# Schematic2_new.net
KiCad netlist of a schematic drawn in Altium Designer
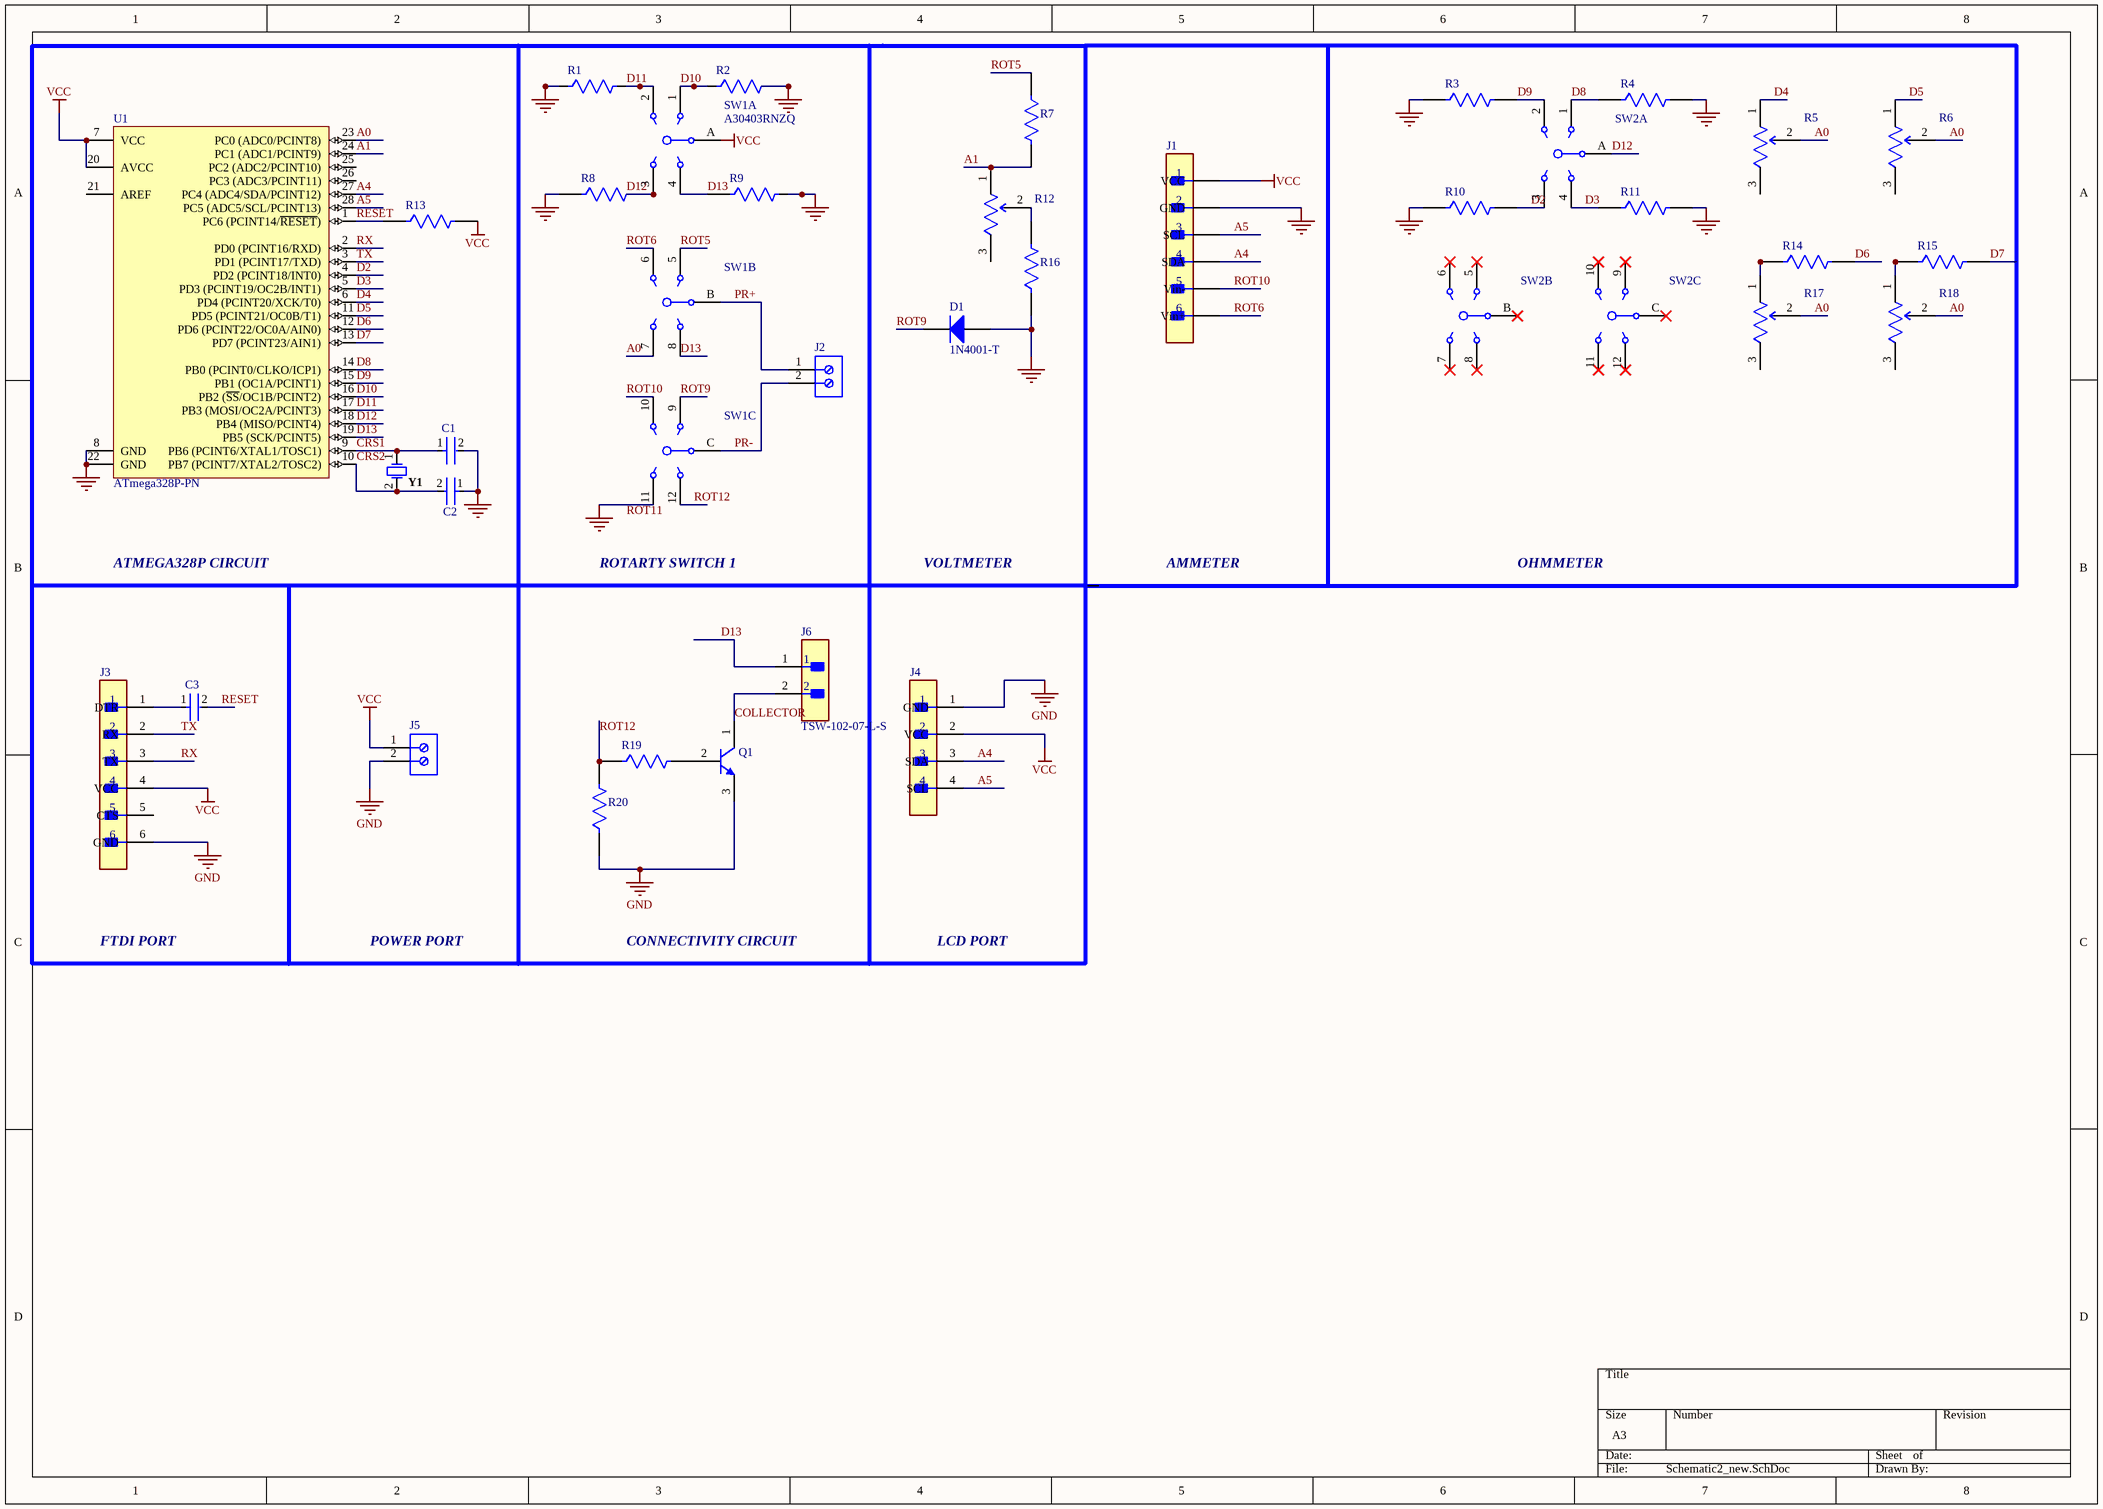
[diagram p0: Schematic2_new.SchDoc]

(export (version "E")
  (design (tool "Eeschema 10.0.6"))
  (components
    (comp (ref "C1")
      (value "RDE5C1H220J0K1H03B")
      (footprint "FP-RDE0M1-MFG")
      (description "Ceramic Capacitor 22pF ±5% 50V C0G Radial")
      (fields (field (name "TOLERANCE") "5%"))
      (libsource (lib "Altium Content Vault") (part "b4654b650e69147ec39a6b967a45e02"))
    )
    (comp (ref "C2")
      (value "RDE5C1H220J0K1H03B")
      (footprint "FP-RDE0M1-MFG")
      (description "Ceramic Capacitor 22pF ±5% 50V C0G Radial")
      (fields (field (name "TOLERANCE") "5%"))
      (libsource (lib "Altium Content Vault") (part "b4654b650e69147ec39a6b967a45e02"))
    )
    (comp (ref "C3")
      (value "RDE5C1H220J0K1H03B")
      (footprint "FP-RDE0M1-MFG")
      (description "Ceramic Capacitor 22pF ±5% 50V C0G Radial")
      (fields (field (name "TOLERANCE") "5%"))
      (libsource (lib "Altium Content Vault") (part "b4654b650e69147ec39a6b967a45e02"))
    )
    (comp (ref "D1")
      (value "1N4001-T")
      (footprint "DIOD-DO-41-P-2_V")
      (description "1.0 A Rectifier, 15 pF, 50 V, -65 to 150 degC, 2-Pin DO-41 Plastic, RoHS, Tape and Reel")
      (fields (field (name "MANUFACTURER") "Diodes Inc"))
      (libsource (lib "Altium Content Vault") (part "DIOD-D-A1K2-2"))
    )
    (comp (ref "J1")
      (value "PEC06SBBN")
      (footprint "FP-PEC06SBBN-MFG")
      (description "CONN HEADER R/A 6POS 2.54MM")
      (libsource (lib "") (part "f2cb566baf1c37ab5a3b8e90bbeafd6_1"))
    )
    (comp (ref "J2")
      (value "691214110002")
      (footprint "691214110002")
      (description "Serie 2141 - 3.50 mm Horizontal Entry Modular with Rising Cage Clamp WR-TBL, 2 pin")
      (fields (field (name "MANUFACTURER") "Wurth Elektronik") (field (name "PUBLISHER") "WurthElektronik"))
      (libsource (lib "Altium Content Vault") (part "WE-CN-1P-F-TB2"))
    )
    (comp (ref "J3")
      (value "PEC06SBBN")
      (footprint "FP-PEC06SBBN-MFG")
      (description "CONN HEADER R/A 6POS 2.54MM")
      (libsource (lib "Altium Content Vault") (part "f2cb566baf1c37ab5a3b8e90bbeafd6"))
    )
    (comp (ref "J4")
      (value "MTLW-104-05-G-S-185")
      (footprint "FP-MTLW-104-05-G-S-185-MFG")
      (description "CONN HEADER VERT 4POS 2.54MM")
      (libsource (lib "Altium Content Vault") (part "299a8cea1bdcbc3624fe62c390fa72c"))
    )
    (comp (ref "J5")
      (value "691214110002")
      (footprint "691214110002")
      (description "Serie 2141 - 3.50 mm Horizontal Entry Modular with Rising Cage Clamp WR-TBL, 2 pin")
      (fields (field (name "MANUFACTURER") "Wurth Elektronik") (field (name "PUBLISHER") "WurthElektronik"))
      (libsource (lib "Altium Content Vault") (part "WE-CN-1P-F-TB2"))
    )
    (comp (ref "J6")
      (value "TSW-102-07-L-S")
      (footprint "FP-TSW-102-07-L-S-MFG")
      (description "CONN HEADER VERT 2POS 2.54MM")
      (libsource (lib "Altium Content Vault") (part "3bc925449376181038e59eaffc5286c"))
    )
    (comp (ref "Q1")
      (value "BC547BRL1G")
      (footprint "ONSC-TO-92-3-29-11_AM_BL")
      (description "Amplifier Transistor, NPN Silicon, 3-Pin TO-92, Pb-Free, Tape and Reel")
      (fields (field (name "MANUFACTURER") "On Semiconductor"))
      (libsource (lib "Altium Content Vault") (part "ONSC-NPN-C1B2E3-3"))
    )
    (comp (ref "R1")
      (value "G001R1000FE1280")
      (footprint "FP-G001R1000FE1280-MFG")
      (description "Res Wirewound 0.1 Ohm 1% 1W ±90ppm/°C Ceramic Hi Temp Sil AXL Thru-Hole Bulk")
      (fields (field (name "TOLERANCE") "1%"))
      (libsource (lib "Altium Content Vault") (part "1029c3af85768c4190bb7ad29bc67b5"))
    )
    (comp (ref "R2")
      (value "G001R1000FE1280")
      (footprint "FP-G001R1000FE1280-MFG")
      (description "Res Wirewound 0.1 Ohm 1% 1W ±90ppm/°C Ceramic Hi Temp Sil AXL Thru-Hole Bulk")
      (fields (field (name "TOLERANCE") "1%"))
      (libsource (lib "Altium Content Vault") (part "1029c3af85768c4190bb7ad29bc67b5"))
    )
    (comp (ref "R3")
      (value "G001R1000FE1280")
      (footprint "FP-G001R1000FE1280-MFG")
      (description "Res Wirewound 0.1 Ohm 1% 1W ±90ppm/°C Ceramic Hi Temp Sil AXL Thru-Hole Bulk")
      (fields (field (name "TOLERANCE") "1%"))
      (libsource (lib "Altium Content Vault") (part "1029c3af85768c4190bb7ad29bc67b5"))
    )
    (comp (ref "R4")
      (value "G001R1000FE1280")
      (footprint "FP-G001R1000FE1280-MFG")
      (description "Res Wirewound 0.1 Ohm 1% 1W ±90ppm/°C Ceramic Hi Temp Sil AXL Thru-Hole Bulk")
      (fields (field (name "TOLERANCE") "1%"))
      (libsource (lib "Altium Content Vault") (part "1029c3af85768c4190bb7ad29bc67b5"))
    )
    (comp (ref "R5")
      (value "3296W-1-103RLF")
      (footprint "FP-3296W-MFG")
      (description "TRIMMER 10K OHM 0.5W PC PIN TOP")
      (fields (field (name "TOLERANCE") "10%"))
      (libsource (lib "Altium Content Vault") (part "194907ebf2981c0cdd5d9631a0af656"))
    )
    (comp (ref "R6")
      (value "3296W-1-103RLF")
      (footprint "FP-3296W-MFG")
      (description "TRIMMER 10K OHM 0.5W PC PIN TOP")
      (fields (field (name "TOLERANCE") "10%"))
      (libsource (lib "Altium Content Vault") (part "194907ebf2981c0cdd5d9631a0af656"))
    )
    (comp (ref "R7")
      (value "G001R1000FE1280")
      (footprint "FP-G001R1000FE1280-MFG")
      (description "Res Wirewound 0.1 Ohm 1% 1W ±90ppm/°C Ceramic Hi Temp Sil AXL Thru-Hole Bulk")
      (fields (field (name "TOLERANCE") "1%"))
      (libsource (lib "Altium Content Vault") (part "1029c3af85768c4190bb7ad29bc67b5"))
    )
    (comp (ref "R8")
      (value "G001R1000FE1280")
      (footprint "FP-G001R1000FE1280-MFG")
      (description "Res Wirewound 0.1 Ohm 1% 1W ±90ppm/°C Ceramic Hi Temp Sil AXL Thru-Hole Bulk")
      (fields (field (name "TOLERANCE") "1%"))
      (libsource (lib "Altium Content Vault") (part "1029c3af85768c4190bb7ad29bc67b5"))
    )
    (comp (ref "R9")
      (value "G001R1000FE1280")
      (footprint "FP-G001R1000FE1280-MFG")
      (description "Res Wirewound 0.1 Ohm 1% 1W ±90ppm/°C Ceramic Hi Temp Sil AXL Thru-Hole Bulk")
      (fields (field (name "TOLERANCE") "1%"))
      (libsource (lib "Altium Content Vault") (part "1029c3af85768c4190bb7ad29bc67b5"))
    )
    (comp (ref "R10")
      (value "G001R1000FE1280")
      (footprint "FP-G001R1000FE1280-MFG")
      (description "Res Wirewound 0.1 Ohm 1% 1W ±90ppm/°C Ceramic Hi Temp Sil AXL Thru-Hole Bulk")
      (fields (field (name "TOLERANCE") "1%"))
      (libsource (lib "Altium Content Vault") (part "1029c3af85768c4190bb7ad29bc67b5"))
    )
    (comp (ref "R11")
      (value "G001R1000FE1280")
      (footprint "FP-G001R1000FE1280-MFG")
      (description "Res Wirewound 0.1 Ohm 1% 1W ±90ppm/°C Ceramic Hi Temp Sil AXL Thru-Hole Bulk")
      (fields (field (name "TOLERANCE") "1%"))
      (libsource (lib "Altium Content Vault") (part "1029c3af85768c4190bb7ad29bc67b5"))
    )
    (comp (ref "R12")
      (value "3296W-1-103RLF")
      (footprint "FP-3296W-MFG")
      (description "TRIMMER 10K OHM 0.5W PC PIN TOP")
      (fields (field (name "TOLERANCE") "10%"))
      (libsource (lib "Altium Content Vault") (part "194907ebf2981c0cdd5d9631a0af656"))
    )
    (comp (ref "R13")
      (value "G001R1000FE1280")
      (footprint "FP-G001R1000FE1280-MFG")
      (description "Res Wirewound 0.1 Ohm 1% 1W ±90ppm/°C Ceramic Hi Temp Sil AXL Thru-Hole Bulk")
      (fields (field (name "TOLERANCE") "1%"))
      (libsource (lib "Altium Content Vault") (part "1029c3af85768c4190bb7ad29bc67b5"))
    )
    (comp (ref "R14")
      (value "G001R1000FE1280")
      (footprint "FP-G001R1000FE1280-MFG")
      (description "Res Wirewound 0.1 Ohm 1% 1W ±90ppm/°C Ceramic Hi Temp Sil AXL Thru-Hole Bulk")
      (fields (field (name "TOLERANCE") "1%"))
      (libsource (lib "Altium Content Vault") (part "1029c3af85768c4190bb7ad29bc67b5"))
    )
    (comp (ref "R15")
      (value "G001R1000FE1280")
      (footprint "FP-G001R1000FE1280-MFG")
      (description "Res Wirewound 0.1 Ohm 1% 1W ±90ppm/°C Ceramic Hi Temp Sil AXL Thru-Hole Bulk")
      (fields (field (name "TOLERANCE") "1%"))
      (libsource (lib "Altium Content Vault") (part "1029c3af85768c4190bb7ad29bc67b5"))
    )
    (comp (ref "R16")
      (value "G001R1000FE1280")
      (footprint "FP-G001R1000FE1280-MFG")
      (description "Res Wirewound 0.1 Ohm 1% 1W ±90ppm/°C Ceramic Hi Temp Sil AXL Thru-Hole Bulk")
      (fields (field (name "TOLERANCE") "1%"))
      (libsource (lib "Altium Content Vault") (part "1029c3af85768c4190bb7ad29bc67b5"))
    )
    (comp (ref "R17")
      (value "3296W-1-103RLF")
      (footprint "FP-3296W-MFG")
      (description "TRIMMER 10K OHM 0.5W PC PIN TOP")
      (fields (field (name "TOLERANCE") "10%"))
      (libsource (lib "Altium Content Vault") (part "194907ebf2981c0cdd5d9631a0af656"))
    )
    (comp (ref "R18")
      (value "3296W-1-103RLF")
      (footprint "FP-3296W-MFG")
      (description "TRIMMER 10K OHM 0.5W PC PIN TOP")
      (fields (field (name "TOLERANCE") "10%"))
      (libsource (lib "Altium Content Vault") (part "194907ebf2981c0cdd5d9631a0af656"))
    )
    (comp (ref "R19")
      (value "G001R1000FE1280")
      (footprint "FP-G001R1000FE1280-MFG")
      (description "Res Wirewound 0.1 Ohm 1% 1W ±90ppm/°C Ceramic Hi Temp Sil AXL Thru-Hole Bulk")
      (fields (field (name "TOLERANCE") "1%"))
      (libsource (lib "Altium Content Vault") (part "1029c3af85768c4190bb7ad29bc67b5"))
    )
    (comp (ref "R20")
      (value "G001R1000FE1280")
      (footprint "FP-G001R1000FE1280-MFG")
      (description "Res Wirewound 0.1 Ohm 1% 1W ±90ppm/°C Ceramic Hi Temp Sil AXL Thru-Hole Bulk")
      (fields (field (name "TOLERANCE") "1%"))
      (libsource (lib "Altium Content Vault") (part "1029c3af85768c4190bb7ad29bc67b5"))
    )
    (comp (ref "SW1")
      (value "A30403RNZQ")
      (footprint "CKCP-A30403RNZQ-15_V")
      (description "A Series Rotary Switch, 3 Poles, 4 Positions, 30 deg Angle of Throw, -30 to 85 degC, RoHS")
      (fields (field (name "MANUFACTURER") "C&K Components"))
      (libsource (lib "") (part "CKCP-SW_3P4T-15_2"))
    )
    (comp (ref "SW2")
      (value "A30403RNZQ")
      (footprint "CKCP-A30403RNZQ-15_V")
      (description "A Series Rotary Switch, 3 Poles, 4 Positions, 30 deg Angle of Throw, -30 to 85 degC, RoHS")
      (fields (field (name "MANUFACTURER") "C&K Components"))
      (libsource (lib "") (part "CKCP-SW_3P4T-15_1"))
    )
    (comp (ref "U1")
      (value "ATmega328P-PN")
      (footprint "28P3")
      (libsource (lib "Altium Content Vault") (part "MC-8B-ATM48-IL28"))
    )
    (comp (ref "Y1")
      (value "FOXSLF/160-20")
      (footprint "FOX-FOXSLF160-20")
      (description "Resistance Weld Thru-Hole Crystal, 16 MHz, -20 to 70 degC, 2-Pin THD, RoHS, Bulk")
      (fields (field (name "TOLERANCE") "1%"))
      (libsource (lib "Altium Content Vault") (part "XTAL-1-2-2"))
    )
  )
  (nets
    (net (code "1") (name "/A0") (class "Default")
      (node (ref "R17") (pin "2") (pinfunction "WIPER_2") (pintype "passive"))
      (node (ref "R18") (pin "2") (pinfunction "WIPER_2") (pintype "passive"))
      (node (ref "R5") (pin "2") (pinfunction "WIPER_2") (pintype "passive"))
      (node (ref "R6") (pin "2") (pinfunction "WIPER_2") (pintype "passive"))
      (node (ref "SW1") (pin "7") (pinfunction "7_7") (pintype "passive"))
      (node (ref "U1") (pin "23") (pinfunction "PC0_(ADC0/PCINT8)_23") (pintype "bidirectional"))
    )
    (net (code "2") (name "/A1") (class "Default")
      (node (ref "R12") (pin "1") (pinfunction "CCW_1") (pintype "passive"))
      (node (ref "R7") (pin "2") (pinfunction "2_2") (pintype "passive"))
      (node (ref "U1") (pin "24") (pinfunction "PC1_(ADC1/PCINT9)_24") (pintype "bidirectional"))
    )
    (net (code "3") (name "/A4") (class "Default")
      (node (ref "J1") (pin "4") (pinfunction "SDA_4") (pintype "passive"))
      (node (ref "J4") (pin "3") (pinfunction "SDA_3") (pintype "passive"))
      (node (ref "U1") (pin "27") (pinfunction "PC4_(ADC4/SDA/PCINT12)_27") (pintype "bidirectional"))
    )
    (net (code "4") (name "/A5") (class "Default")
      (node (ref "J1") (pin "3") (pinfunction "SCL_3") (pintype "passive"))
      (node (ref "J4") (pin "4") (pinfunction "SCL_4") (pintype "passive"))
      (node (ref "U1") (pin "28") (pinfunction "PC5_(ADC5/SCL/PCINT13)_28") (pintype "bidirectional"))
    )
    (net (code "5") (name "/COLLECTOR") (class "Default")
      (node (ref "J6") (pin "2") (pinfunction "2_2") (pintype "passive"))
      (node (ref "Q1") (pin "1") (pinfunction "C_1") (pintype "passive"))
    )
    (net (code "6") (name "/CRS1") (class "Default")
      (node (ref "C1") (pin "1") (pinfunction "1_1") (pintype "passive"))
      (node (ref "U1") (pin "9") (pinfunction "PB6_(PCINT6/XTAL1/TOSC1)_9") (pintype "bidirectional"))
      (node (ref "Y1") (pin "1") (pinfunction "1_1") (pintype "passive"))
    )
    (net (code "7") (name "/CRS2") (class "Default")
      (node (ref "C2") (pin "2") (pinfunction "2_2") (pintype "passive"))
      (node (ref "U1") (pin "10") (pinfunction "PB7_(PCINT7/XTAL2/TOSC2)_10") (pintype "bidirectional"))
      (node (ref "Y1") (pin "2") (pinfunction "2_2") (pintype "passive"))
    )
    (net (code "8") (name "/D2") (class "Default")
      (node (ref "R10") (pin "2") (pinfunction "2_2") (pintype "passive"))
      (node (ref "SW2") (pin "3") (pinfunction "3_3") (pintype "passive"))
      (node (ref "U1") (pin "4") (pinfunction "PD2_(PCINT18/INT0)_4") (pintype "bidirectional"))
    )
    (net (code "9") (name "/D3") (class "Default")
      (node (ref "R11") (pin "1") (pinfunction "1_1") (pintype "passive"))
      (node (ref "SW2") (pin "4") (pinfunction "4_4") (pintype "passive"))
      (node (ref "U1") (pin "5") (pinfunction "PD3_(PCINT19/OC2B/INT1)_5") (pintype "bidirectional"))
    )
    (net (code "10") (name "/D4") (class "Default")
      (node (ref "R5") (pin "1") (pinfunction "CCW_1") (pintype "passive"))
      (node (ref "U1") (pin "6") (pinfunction "PD4_(PCINT20/XCK/T0)_6") (pintype "bidirectional"))
    )
    (net (code "11") (name "/D5") (class "Default")
      (node (ref "R6") (pin "1") (pinfunction "CCW_1") (pintype "passive"))
      (node (ref "U1") (pin "11") (pinfunction "PD5_(PCINT21/OC0B/T1)_11") (pintype "bidirectional"))
    )
    (net (code "12") (name "/D6") (class "Default")
      (node (ref "R14") (pin "2") (pinfunction "2_2") (pintype "passive"))
      (node (ref "U1") (pin "12") (pinfunction "PD6_(PCINT22/OC0A/AIN0)_12") (pintype "bidirectional"))
    )
    (net (code "13") (name "/D7") (class "Default")
      (node (ref "R15") (pin "2") (pinfunction "2_2") (pintype "passive"))
      (node (ref "U1") (pin "13") (pinfunction "PD7_(PCINT23/AIN1)_13") (pintype "bidirectional"))
    )
    (net (code "14") (name "/D8") (class "Default")
      (node (ref "R4") (pin "1") (pinfunction "1_1") (pintype "passive"))
      (node (ref "SW2") (pin "1") (pinfunction "1_1") (pintype "passive"))
      (node (ref "U1") (pin "14") (pinfunction "PB0_(PCINT0/CLKO/ICP1)_14") (pintype "bidirectional"))
    )
    (net (code "15") (name "/D9") (class "Default")
      (node (ref "R3") (pin "2") (pinfunction "2_2") (pintype "passive"))
      (node (ref "SW2") (pin "2") (pinfunction "2_2") (pintype "passive"))
      (node (ref "U1") (pin "15") (pinfunction "PB1_(OC1A/PCINT1)_15") (pintype "bidirectional"))
    )
    (net (code "16") (name "/D10") (class "Default")
      (node (ref "R2") (pin "1") (pinfunction "1_1") (pintype "passive"))
      (node (ref "SW1") (pin "1") (pinfunction "1_1") (pintype "passive"))
      (node (ref "U1") (pin "16") (pinfunction "PB2_(~{SS}/OC1B/PCINT2)_16") (pintype "bidirectional"))
    )
    (net (code "17") (name "/D11") (class "Default")
      (node (ref "R1") (pin "2") (pinfunction "2_2") (pintype "passive"))
      (node (ref "SW1") (pin "2") (pinfunction "2_2") (pintype "passive"))
      (node (ref "U1") (pin "17") (pinfunction "PB3_(MOSI/OC2A/PCINT3)_17") (pintype "bidirectional"))
    )
    (net (code "18") (name "/D12") (class "Default")
      (node (ref "R8") (pin "2") (pinfunction "2_2") (pintype "passive"))
      (node (ref "SW1") (pin "3") (pinfunction "3_3") (pintype "passive"))
      (node (ref "SW2") (pin "A") (pinfunction "A_A") (pintype "passive"))
      (node (ref "U1") (pin "18") (pinfunction "PB4_(MISO/PCINT4)_18") (pintype "bidirectional"))
    )
    (net (code "19") (name "/D13") (class "Default")
      (node (ref "J6") (pin "1") (pinfunction "1_1") (pintype "passive"))
      (node (ref "R9") (pin "1") (pinfunction "1_1") (pintype "passive"))
      (node (ref "SW1") (pin "4") (pinfunction "4_4") (pintype "passive"))
      (node (ref "SW1") (pin "8") (pinfunction "8_8") (pintype "passive"))
      (node (ref "U1") (pin "19") (pinfunction "PB5_(SCK/PCINT5)_19") (pintype "bidirectional"))
    )
    (net (code "20") (name "/PR+") (class "Default")
      (node (ref "J2") (pin "1") (pinfunction "1_1") (pintype "passive"))
      (node (ref "SW1") (pin "B") (pinfunction "B_B") (pintype "passive"))
    )
    (net (code "21") (name "/PR-") (class "Default")
      (node (ref "J2") (pin "2") (pinfunction "2_2") (pintype "passive"))
      (node (ref "SW1") (pin "C") (pinfunction "C_C") (pintype "passive"))
    )
    (net (code "22") (name "/RESET") (class "Default")
      (node (ref "C3") (pin "2") (pinfunction "2_2") (pintype "passive"))
      (node (ref "R13") (pin "1") (pinfunction "1_1") (pintype "passive"))
      (node (ref "U1") (pin "1") (pinfunction "PC6_(PCINT14/~{RESET})_1") (pintype "bidirectional"))
    )
    (net (code "23") (name "/ROT5") (class "Default")
      (node (ref "R7") (pin "1") (pinfunction "1_1") (pintype "passive"))
      (node (ref "SW1") (pin "5") (pinfunction "5_5") (pintype "passive"))
    )
    (net (code "24") (name "/ROT6") (class "Default")
      (node (ref "J1") (pin "6") (pinfunction "Vin+_6") (pintype "passive"))
      (node (ref "SW1") (pin "6") (pinfunction "6_6") (pintype "passive"))
    )
    (net (code "25") (name "/ROT9") (class "Default")
      (node (ref "D1") (pin "2") (pinfunction "K_2") (pintype "passive"))
      (node (ref "SW1") (pin "9") (pinfunction "9_9") (pintype "passive"))
    )
    (net (code "26") (name "/ROT10") (class "Default")
      (node (ref "J1") (pin "5") (pinfunction "Vin-_5") (pintype "passive"))
      (node (ref "SW1") (pin "10") (pinfunction "10_10") (pintype "passive"))
    )
    (net (code "28") (name "/ROT12") (class "Default")
      (node (ref "R19") (pin "1") (pinfunction "1_1") (pintype "passive"))
      (node (ref "R20") (pin "2") (pinfunction "2_2") (pintype "passive"))
      (node (ref "SW1") (pin "12") (pinfunction "12_12") (pintype "passive"))
    )
    (net (code "29") (name "/RX") (class "Default")
      (node (ref "J3") (pin "3") (pinfunction "TX_3") (pintype "passive"))
      (node (ref "U1") (pin "2") (pinfunction "PD0_(PCINT16/RXD)_2") (pintype "bidirectional"))
    )
    (net (code "30") (name "/TX") (class "Default")
      (node (ref "J3") (pin "2") (pinfunction "RX_2") (pintype "passive"))
      (node (ref "U1") (pin "3") (pinfunction "PD1_(PCINT17/TXD)_3") (pintype "bidirectional"))
    )
    (net (code "31") (name "GND") (class "Default")
      (node (ref "C1") (pin "2") (pinfunction "2_2") (pintype "passive"))
      (node (ref "C2") (pin "1") (pinfunction "1_1") (pintype "passive"))
      (node (ref "D1") (pin "1") (pinfunction "A_1") (pintype "passive"))
      (node (ref "J1") (pin "2") (pinfunction "GND_2") (pintype "passive"))
      (node (ref "J3") (pin "6") (pinfunction "GND_6") (pintype "passive"))
      (node (ref "J4") (pin "1") (pinfunction "GND_1") (pintype "passive"))
      (node (ref "J5") (pin "2") (pinfunction "2_2") (pintype "passive"))
      (node (ref "Q1") (pin "3") (pinfunction "E_3") (pintype "passive"))
      (node (ref "R1") (pin "1") (pinfunction "1_1") (pintype "passive"))
      (node (ref "R10") (pin "1") (pinfunction "1_1") (pintype "passive"))
      (node (ref "R11") (pin "2") (pinfunction "2_2") (pintype "passive"))
      (node (ref "R16") (pin "1") (pinfunction "1_1") (pintype "passive"))
      (node (ref "R2") (pin "2") (pinfunction "2_2") (pintype "passive"))
      (node (ref "R20") (pin "1") (pinfunction "1_1") (pintype "passive"))
      (node (ref "R3") (pin "1") (pinfunction "1_1") (pintype "passive"))
      (node (ref "R4") (pin "2") (pinfunction "2_2") (pintype "passive"))
      (node (ref "R8") (pin "1") (pinfunction "1_1") (pintype "passive"))
      (node (ref "R9") (pin "2") (pinfunction "2_2") (pintype "passive"))
      (node (ref "SW1") (pin "11") (pinfunction "11_11") (pintype "passive"))
      (node (ref "U1") (pin "22") (pinfunction "GND_22") (pintype "power_in"))
      (node (ref "U1") (pin "8") (pinfunction "GND_8") (pintype "power_in"))
    )
    (net (code "32") (name "Net-(J3-DTR)") (class "Default")
      (node (ref "C3") (pin "1") (pinfunction "1_1") (pintype "passive"))
      (node (ref "J3") (pin "1") (pinfunction "DTR_1") (pintype "passive"))
    )
    (net (code "33") (name "Net-(Q1-B)") (class "Default")
      (node (ref "Q1") (pin "2") (pinfunction "B_2") (pintype "passive"))
      (node (ref "R19") (pin "2") (pinfunction "2_2") (pintype "passive"))
    )
    (net (code "34") (name "Net-(R12-WIPER)") (class "Default")
      (node (ref "R12") (pin "2") (pinfunction "WIPER_2") (pintype "passive"))
      (node (ref "R16") (pin "2") (pinfunction "2_2") (pintype "passive"))
    )
    (net (code "35") (name "Net-(R17-CCW)") (class "Default")
      (node (ref "R14") (pin "1") (pinfunction "1_1") (pintype "passive"))
      (node (ref "R17") (pin "1") (pinfunction "CCW_1") (pintype "passive"))
    )
    (net (code "36") (name "Net-(R18-CCW)") (class "Default")
      (node (ref "R15") (pin "1") (pinfunction "1_1") (pintype "passive"))
      (node (ref "R18") (pin "1") (pinfunction "CCW_1") (pintype "passive"))
    )
    (net (code "37") (name "VCC") (class "Default")
      (node (ref "J1") (pin "1") (pinfunction "VCC_1") (pintype "passive"))
      (node (ref "J3") (pin "4") (pinfunction "VCC_4") (pintype "passive"))
      (node (ref "J4") (pin "2") (pinfunction "VCC_2") (pintype "passive"))
      (node (ref "J5") (pin "1") (pinfunction "1_1") (pintype "passive"))
      (node (ref "R13") (pin "2") (pinfunction "2_2") (pintype "passive"))
      (node (ref "SW1") (pin "A") (pinfunction "A_A") (pintype "passive"))
      (node (ref "U1") (pin "20") (pinfunction "AVCC_20") (pintype "power_in"))
      (node (ref "U1") (pin "7") (pinfunction "VCC_7") (pintype "power_in"))
    )
    (net (code "38") (name "unconnected-(J3-CTS-Pad5)") (class "Default")
      (node (ref "J3") (pin "5") (pinfunction "CTS_5") (pintype "passive"))
    )
    (net (code "39") (name "unconnected-(R5-CW-Pad3)") (class "Default")
      (node (ref "R5") (pin "3") (pinfunction "CW_3") (pintype "passive"))
    )
    (net (code "40") (name "unconnected-(R6-CW-Pad3)") (class "Default")
      (node (ref "R6") (pin "3") (pinfunction "CW_3") (pintype "passive"))
    )
    (net (code "41") (name "unconnected-(R12-CW-Pad3)") (class "Default")
      (node (ref "R12") (pin "3") (pinfunction "CW_3") (pintype "passive"))
    )
    (net (code "42") (name "unconnected-(R17-CW-Pad3)") (class "Default")
      (node (ref "R17") (pin "3") (pinfunction "CW_3") (pintype "passive"))
    )
    (net (code "43") (name "unconnected-(R18-CW-Pad3)") (class "Default")
      (node (ref "R18") (pin "3") (pinfunction "CW_3") (pintype "passive"))
    )
    (net (code "44") (name "unconnected-(SW2-Pad5)") (class "Default")
      (node (ref "SW2") (pin "5") (pinfunction "5_5") (pintype "passive+no_connect"))
    )
    (net (code "45") (name "unconnected-(SW2-Pad6)") (class "Default")
      (node (ref "SW2") (pin "6") (pinfunction "6_6") (pintype "passive+no_connect"))
    )
    (net (code "46") (name "unconnected-(SW2-Pad7)") (class "Default")
      (node (ref "SW2") (pin "7") (pinfunction "7_7") (pintype "passive+no_connect"))
    )
    (net (code "47") (name "unconnected-(SW2-Pad8)") (class "Default")
      (node (ref "SW2") (pin "8") (pinfunction "8_8") (pintype "passive+no_connect"))
    )
    (net (code "48") (name "unconnected-(SW2-Pad9)") (class "Default")
      (node (ref "SW2") (pin "9") (pinfunction "9_9") (pintype "passive+no_connect"))
    )
    (net (code "49") (name "unconnected-(SW2-Pad10)") (class "Default")
      (node (ref "SW2") (pin "10") (pinfunction "10_10") (pintype "passive+no_connect"))
    )
    (net (code "50") (name "unconnected-(SW2-Pad11)") (class "Default")
      (node (ref "SW2") (pin "11") (pinfunction "11_11") (pintype "passive+no_connect"))
    )
    (net (code "51") (name "unconnected-(SW2-Pad12)") (class "Default")
      (node (ref "SW2") (pin "12") (pinfunction "12_12") (pintype "passive+no_connect"))
    )
    (net (code "52") (name "unconnected-(SW2-PadB)") (class "Default")
      (node (ref "SW2") (pin "B") (pinfunction "B_B") (pintype "passive+no_connect"))
    )
    (net (code "53") (name "unconnected-(SW2-PadC)") (class "Default")
      (node (ref "SW2") (pin "C") (pinfunction "C_C") (pintype "passive+no_connect"))
    )
    (net (code "54") (name "unconnected-(U1-AREF-Pad21)") (class "Default")
      (node (ref "U1") (pin "21") (pinfunction "AREF_21") (pintype "power_in"))
    )
    (net (code "55") (name "unconnected-(U1-PC2_(ADC2{slash}PCINT10)-Pad25)") (class "Default")
      (node (ref "U1") (pin "25") (pinfunction "PC2_(ADC2/PCINT10)_25") (pintype "bidirectional"))
    )
    (net (code "56") (name "unconnected-(U1-PC3_(ADC3{slash}PCINT11)-Pad26)") (class "Default")
      (node (ref "U1") (pin "26") (pinfunction "PC3_(ADC3/PCINT11)_26") (pintype "bidirectional"))
    )
  )
)
